# EGB220_Team2.net
KiCad netlist of a schematic drawn in EAGLE
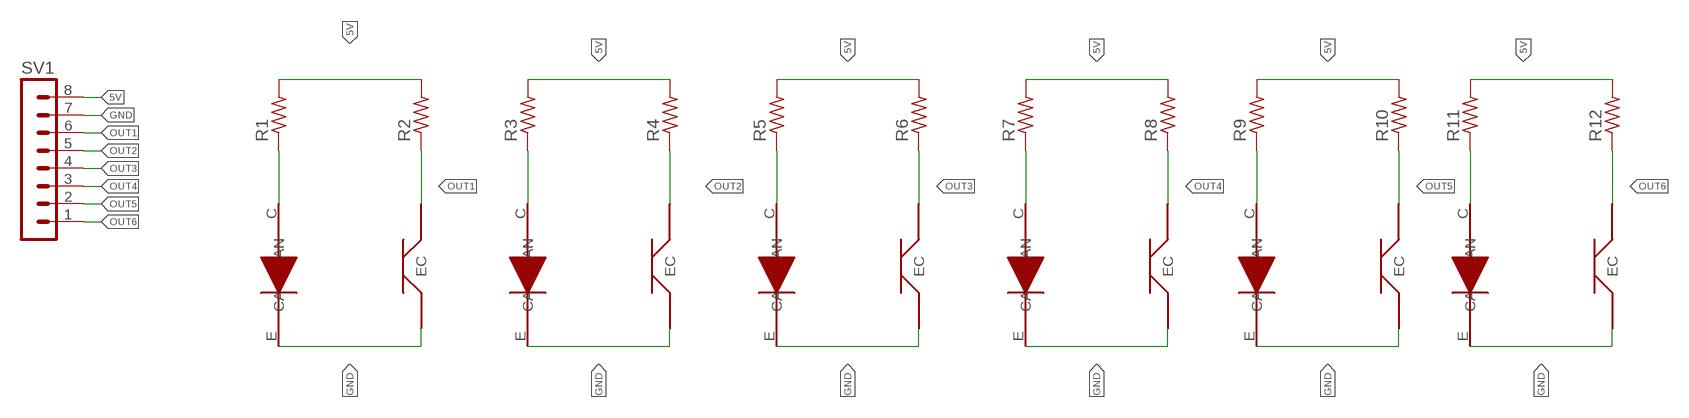
[diagram p0: schematic, sheet 1]

(export (version "E")
  (design (tool "Eeschema 10.0.6"))
  (components
    (comp (ref "LED-R1")
      (value "LED")
      (footprint "eagle-import:PHOTO-DIODE")
      (libsource (lib "eagle-import") (part "LED"))
    )
    (comp (ref "LED-R3")
      (value "LED")
      (footprint "eagle-import:PHOTO-DIODE")
      (libsource (lib "eagle-import") (part "LED"))
    )
    (comp (ref "LED-R5")
      (value "LED")
      (footprint "eagle-import:PHOTO-DIODE")
      (libsource (lib "eagle-import") (part "LED"))
    )
    (comp (ref "LED-R7")
      (value "LED")
      (footprint "eagle-import:PHOTO-DIODE")
      (libsource (lib "eagle-import") (part "LED"))
    )
    (comp (ref "LED-R9")
      (value "LED")
      (footprint "eagle-import:PHOTO-DIODE")
      (libsource (lib "eagle-import") (part "LED"))
    )
    (comp (ref "LED-R11")
      (value "LED")
      (footprint "eagle-import:PHOTO-DIODE")
      (libsource (lib "eagle-import") (part "LED"))
    )
    (comp (ref "R1")
      (value "R-US_0204/7")
      (footprint "eagle-import:0204_7")
      (libsource (lib "eagle-import") (part "R-US_0204/7"))
    )
    (comp (ref "R2")
      (value "R-US_0204/7")
      (footprint "eagle-import:0204_7")
      (libsource (lib "eagle-import") (part "R-US_0204/7"))
    )
    (comp (ref "R3")
      (value "R-US_0204/7")
      (footprint "eagle-import:0204_7")
      (libsource (lib "eagle-import") (part "R-US_0204/7"))
    )
    (comp (ref "R4")
      (value "R-US_0204/7")
      (footprint "eagle-import:0204_7")
      (libsource (lib "eagle-import") (part "R-US_0204/7"))
    )
    (comp (ref "R5")
      (value "R-US_0204/7")
      (footprint "eagle-import:0204_7")
      (libsource (lib "eagle-import") (part "R-US_0204/7"))
    )
    (comp (ref "R6")
      (value "R-US_0204/7")
      (footprint "eagle-import:0204_7")
      (libsource (lib "eagle-import") (part "R-US_0204/7"))
    )
    (comp (ref "R7")
      (value "R-US_0204/7")
      (footprint "eagle-import:0204_7")
      (libsource (lib "eagle-import") (part "R-US_0204/7"))
    )
    (comp (ref "R8")
      (value "R-US_0204/7")
      (footprint "eagle-import:0204_7")
      (libsource (lib "eagle-import") (part "R-US_0204/7"))
    )
    (comp (ref "R9")
      (value "R-US_0204/7")
      (footprint "eagle-import:0204_7")
      (libsource (lib "eagle-import") (part "R-US_0204/7"))
    )
    (comp (ref "R10")
      (value "R-US_0204/7")
      (footprint "eagle-import:0204_7")
      (libsource (lib "eagle-import") (part "R-US_0204/7"))
    )
    (comp (ref "R11")
      (value "R-US_0204/7")
      (footprint "eagle-import:0204_7")
      (libsource (lib "eagle-import") (part "R-US_0204/7"))
    )
    (comp (ref "R12")
      (value "R-US_0204/7")
      (footprint "eagle-import:0204_7")
      (libsource (lib "eagle-import") (part "R-US_0204/7"))
    )
    (comp (ref "SV1")
      (value "MA08-1")
      (footprint "eagle-import:MA08-1")
      (libsource (lib "eagle-import") (part "MA08-1"))
    )
    (comp (ref "T-R2")
      (value "PHOTO_DIODE")
      (footprint "eagle-import:PHOTO-DIODE")
      (libsource (lib "eagle-import") (part "PHOTO_DIODE"))
    )
    (comp (ref "T-R4")
      (value "PHOTO_DIODE")
      (footprint "eagle-import:PHOTO-DIODE")
      (libsource (lib "eagle-import") (part "PHOTO_DIODE"))
    )
    (comp (ref "T-R6")
      (value "PHOTO_DIODE")
      (footprint "eagle-import:PHOTO-DIODE")
      (libsource (lib "eagle-import") (part "PHOTO_DIODE"))
    )
    (comp (ref "T-R8")
      (value "PHOTO_DIODE")
      (footprint "eagle-import:PHOTO-DIODE")
      (libsource (lib "eagle-import") (part "PHOTO_DIODE"))
    )
    (comp (ref "T-R10")
      (value "PHOTO_DIODE")
      (footprint "eagle-import:PHOTO-DIODE")
      (libsource (lib "eagle-import") (part "PHOTO_DIODE"))
    )
    (comp (ref "T-R12")
      (value "PHOTO_DIODE")
      (footprint "eagle-import:PHOTO-DIODE")
      (libsource (lib "eagle-import") (part "PHOTO_DIODE"))
    )
  )
  (nets
    (net (code "1") (name "5V") (class "Default")
      (node (ref "R1") (pin "2") (pinfunction "2_2") (pintype "passive"))
      (node (ref "R10") (pin "2") (pinfunction "2_2") (pintype "passive"))
      (node (ref "R11") (pin "2") (pinfunction "2_2") (pintype "passive"))
      (node (ref "R12") (pin "2") (pinfunction "2_2") (pintype "passive"))
      (node (ref "R2") (pin "2") (pinfunction "2_2") (pintype "passive"))
      (node (ref "R3") (pin "2") (pinfunction "2_2") (pintype "passive"))
      (node (ref "R4") (pin "2") (pinfunction "2_2") (pintype "passive"))
      (node (ref "R5") (pin "2") (pinfunction "2_2") (pintype "passive"))
      (node (ref "R6") (pin "2") (pinfunction "2_2") (pintype "passive"))
      (node (ref "R7") (pin "2") (pinfunction "2_2") (pintype "passive"))
      (node (ref "R8") (pin "2") (pinfunction "2_2") (pintype "passive"))
      (node (ref "R9") (pin "2") (pinfunction "2_2") (pintype "passive"))
      (node (ref "SV1") (pin "8") (pinfunction "8_8") (pintype "passive"))
    )
    (net (code "2") (name "GND") (class "Default")
      (node (ref "LED-R1") (pin "E") (pinfunction "CA_E") (pintype "bidirectional"))
      (node (ref "LED-R11") (pin "E") (pinfunction "CA_E") (pintype "bidirectional"))
      (node (ref "LED-R3") (pin "E") (pinfunction "CA_E") (pintype "bidirectional"))
      (node (ref "LED-R5") (pin "E") (pinfunction "CA_E") (pintype "bidirectional"))
      (node (ref "LED-R7") (pin "E") (pinfunction "CA_E") (pintype "bidirectional"))
      (node (ref "LED-R9") (pin "E") (pinfunction "CA_E") (pintype "bidirectional"))
      (node (ref "SV1") (pin "7") (pinfunction "7_7") (pintype "passive"))
      (node (ref "T-R10") (pin "E") (pinfunction "E_E") (pintype "bidirectional"))
      (node (ref "T-R12") (pin "E") (pinfunction "E_E") (pintype "bidirectional"))
      (node (ref "T-R2") (pin "E") (pinfunction "E_E") (pintype "bidirectional"))
      (node (ref "T-R4") (pin "E") (pinfunction "E_E") (pintype "bidirectional"))
      (node (ref "T-R6") (pin "E") (pinfunction "E_E") (pintype "bidirectional"))
      (node (ref "T-R8") (pin "E") (pinfunction "E_E") (pintype "bidirectional"))
    )
    (net (code "3") (name "Net-(LED-R1-AN)") (class "Default")
      (node (ref "LED-R1") (pin "C") (pinfunction "AN_C") (pintype "bidirectional"))
      (node (ref "R1") (pin "1") (pinfunction "1_1") (pintype "passive"))
    )
    (net (code "4") (name "Net-(LED-R3-AN)") (class "Default")
      (node (ref "LED-R3") (pin "C") (pinfunction "AN_C") (pintype "bidirectional"))
      (node (ref "R3") (pin "1") (pinfunction "1_1") (pintype "passive"))
    )
    (net (code "5") (name "Net-(LED-R5-AN)") (class "Default")
      (node (ref "LED-R5") (pin "C") (pinfunction "AN_C") (pintype "bidirectional"))
      (node (ref "R5") (pin "1") (pinfunction "1_1") (pintype "passive"))
    )
    (net (code "6") (name "Net-(LED-R7-AN)") (class "Default")
      (node (ref "LED-R7") (pin "C") (pinfunction "AN_C") (pintype "bidirectional"))
      (node (ref "R7") (pin "1") (pinfunction "1_1") (pintype "passive"))
    )
    (net (code "7") (name "Net-(LED-R9-AN)") (class "Default")
      (node (ref "LED-R9") (pin "C") (pinfunction "AN_C") (pintype "bidirectional"))
      (node (ref "R9") (pin "1") (pinfunction "1_1") (pintype "passive"))
    )
    (net (code "8") (name "Net-(LED-R11-AN)") (class "Default")
      (node (ref "LED-R11") (pin "C") (pinfunction "AN_C") (pintype "bidirectional"))
      (node (ref "R11") (pin "1") (pinfunction "1_1") (pintype "passive"))
    )
    (net (code "9") (name "OUT1") (class "Default")
      (node (ref "R2") (pin "1") (pinfunction "1_1") (pintype "passive"))
      (node (ref "SV1") (pin "6") (pinfunction "6_6") (pintype "passive"))
      (node (ref "T-R2") (pin "C") (pinfunction "C_C") (pintype "bidirectional"))
    )
    (net (code "10") (name "OUT2") (class "Default")
      (node (ref "R4") (pin "1") (pinfunction "1_1") (pintype "passive"))
      (node (ref "SV1") (pin "5") (pinfunction "5_5") (pintype "passive"))
      (node (ref "T-R4") (pin "C") (pinfunction "C_C") (pintype "bidirectional"))
    )
    (net (code "11") (name "OUT3") (class "Default")
      (node (ref "R6") (pin "1") (pinfunction "1_1") (pintype "passive"))
      (node (ref "SV1") (pin "4") (pinfunction "4_4") (pintype "passive"))
      (node (ref "T-R6") (pin "C") (pinfunction "C_C") (pintype "bidirectional"))
    )
    (net (code "12") (name "OUT4") (class "Default")
      (node (ref "R8") (pin "1") (pinfunction "1_1") (pintype "passive"))
      (node (ref "SV1") (pin "3") (pinfunction "3_3") (pintype "passive"))
      (node (ref "T-R8") (pin "C") (pinfunction "C_C") (pintype "bidirectional"))
    )
    (net (code "13") (name "OUT5") (class "Default")
      (node (ref "R10") (pin "1") (pinfunction "1_1") (pintype "passive"))
      (node (ref "SV1") (pin "2") (pinfunction "2_2") (pintype "passive"))
      (node (ref "T-R10") (pin "C") (pinfunction "C_C") (pintype "bidirectional"))
    )
    (net (code "14") (name "OUT6") (class "Default")
      (node (ref "R12") (pin "1") (pinfunction "1_1") (pintype "passive"))
      (node (ref "SV1") (pin "1") (pinfunction "1_1") (pintype "passive"))
      (node (ref "T-R12") (pin "C") (pinfunction "C_C") (pintype "bidirectional"))
    )
  )
)
